# 7688_kernel.net
KiCad netlist of a schematic drawn in Altium Designer
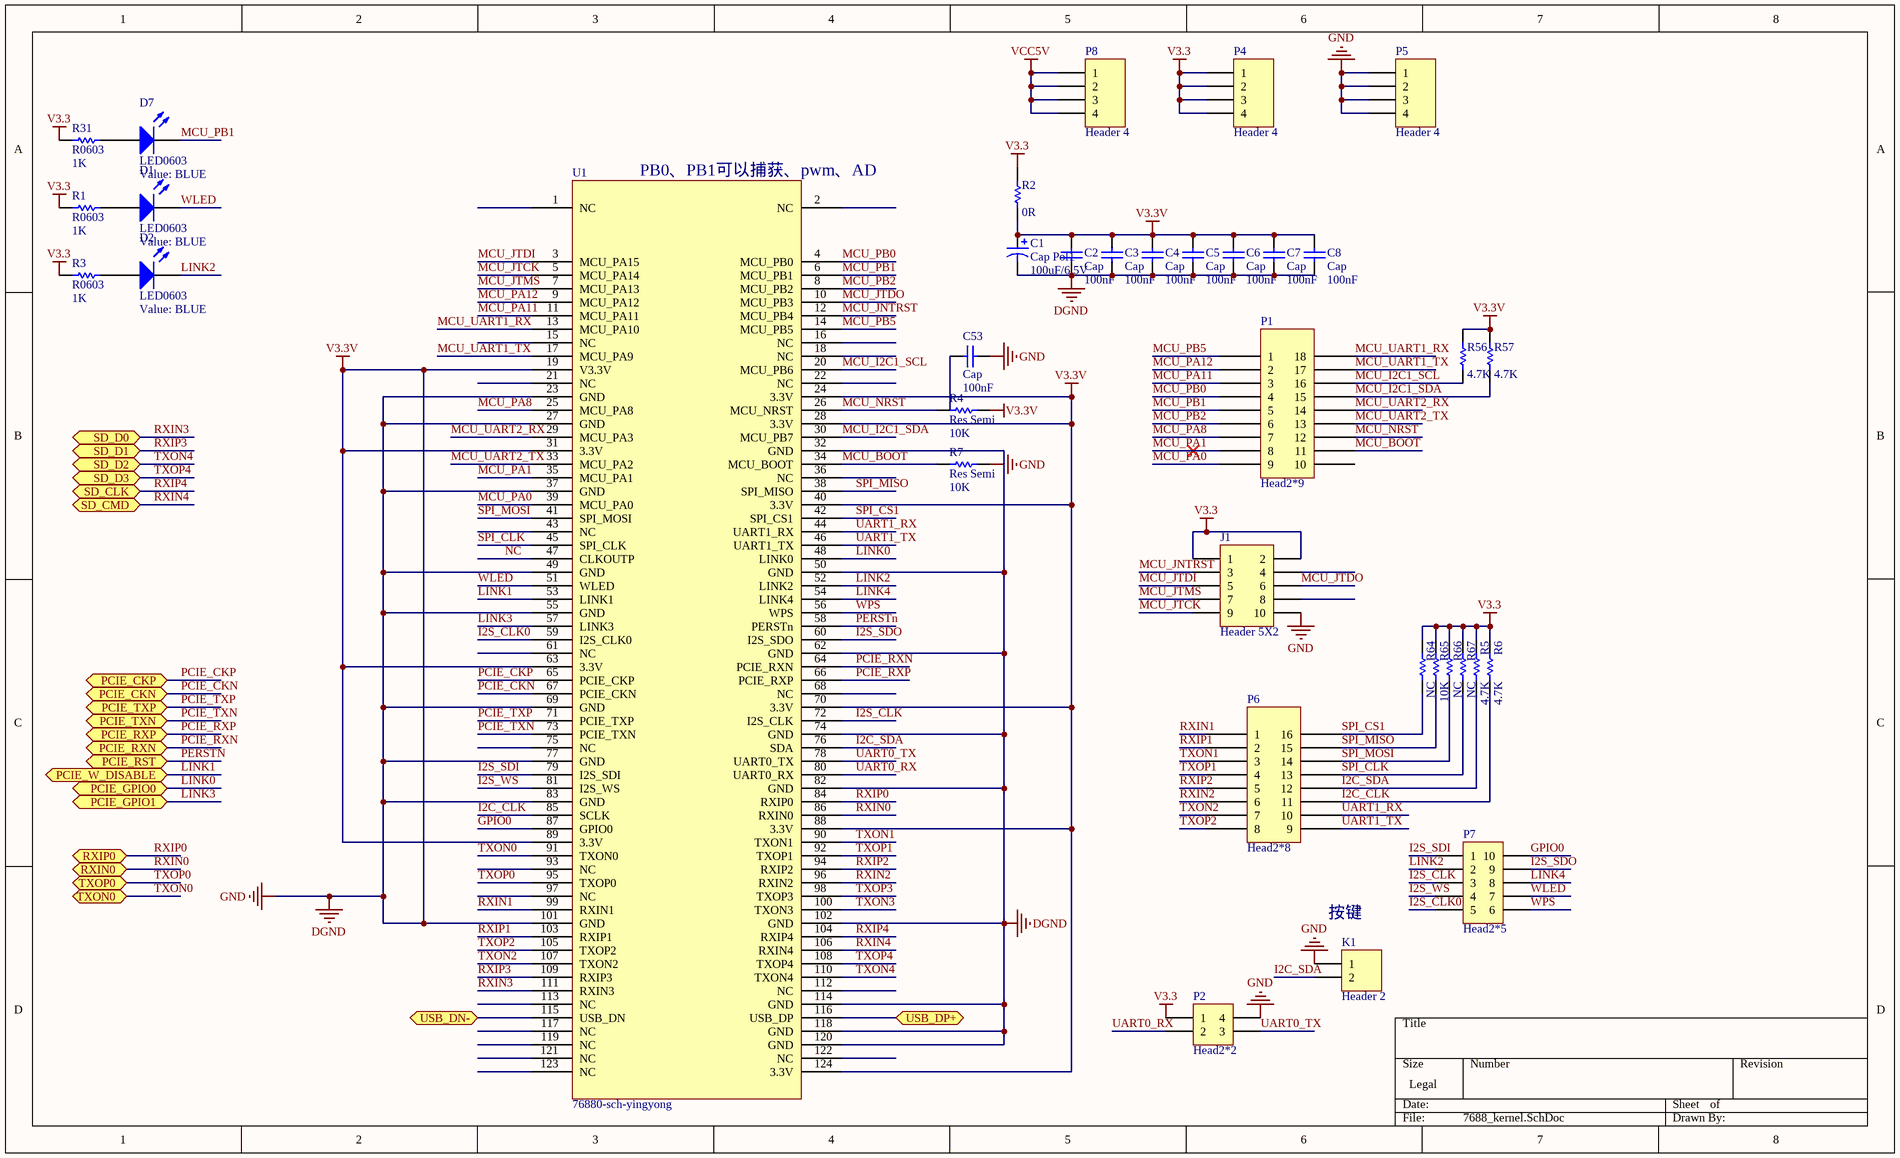
[diagram p0: 7688_kernel.SchDoc]

(export (version "E")
  (design (tool "Eeschema 10.0.6"))
  (components
    (comp (ref "C1")
      (value "Cap Pol1")
      (footprint "C1210-A")
      (description "Polarized Capacitor (Radial)")
      (fields (field (name "ALTIUM_VALUE") "100uF/6.5V") (field (name "PUBLISHER") "Altium Limited"))
      (libsource (lib "Miscellaneous Devices") (part "Cap Pol1"))
    )
    (comp (ref "C2")
      (value "Cap")
      (footprint "R0603N")
      (description "Capacitor")
      (fields (field (name "ALTIUM_VALUE") "100nF") (field (name "PUBLISHER") "Altium Limited"))
      (libsource (lib "Miscellaneous Devices") (part "Cap"))
    )
    (comp (ref "C3")
      (value "Cap")
      (footprint "R0603N")
      (description "Capacitor")
      (fields (field (name "ALTIUM_VALUE") "100nF") (field (name "PUBLISHER") "Altium Limited"))
      (libsource (lib "Miscellaneous Devices") (part "Cap"))
    )
    (comp (ref "C4")
      (value "Cap")
      (footprint "R0603N")
      (description "Capacitor")
      (fields (field (name "ALTIUM_VALUE") "100nF") (field (name "PUBLISHER") "Altium Limited"))
      (libsource (lib "Miscellaneous Devices") (part "Cap"))
    )
    (comp (ref "C5")
      (value "Cap")
      (footprint "R0603N")
      (description "Capacitor")
      (fields (field (name "ALTIUM_VALUE") "100nF") (field (name "PUBLISHER") "Altium Limited"))
      (libsource (lib "Miscellaneous Devices") (part "Cap"))
    )
    (comp (ref "C6")
      (value "Cap")
      (footprint "R0603N")
      (description "Capacitor")
      (fields (field (name "ALTIUM_VALUE") "100nF") (field (name "PUBLISHER") "Altium Limited"))
      (libsource (lib "Miscellaneous Devices") (part "Cap"))
    )
    (comp (ref "C7")
      (value "Cap")
      (footprint "R0603N")
      (description "Capacitor")
      (fields (field (name "ALTIUM_VALUE") "100nF") (field (name "PUBLISHER") "Altium Limited"))
      (libsource (lib "Miscellaneous Devices") (part "Cap"))
    )
    (comp (ref "C8")
      (value "Cap")
      (footprint "R0603N")
      (description "Capacitor")
      (fields (field (name "ALTIUM_VALUE") "100nF") (field (name "PUBLISHER") "Altium Limited"))
      (libsource (lib "Miscellaneous Devices") (part "Cap"))
    )
    (comp (ref "C53")
      (value "Cap")
      (footprint "R0603N")
      (description "Capacitor")
      (fields (field (name "ALTIUM_VALUE") "100nF") (field (name "PUBLISHER") "Altium Limited"))
      (libsource (lib "Miscellaneous Devices") (part "Cap"))
    )
    (comp (ref "D1")
      (value "LED0603")
      (footprint "LED0603")
      (description "LED")
      (fields (field (name "ALTIUM_VALUE") "BLUE"))
      (libsource (lib "schumyhao's_Device") (part "LED"))
    )
    (comp (ref "D2")
      (value "LED0603")
      (footprint "LED0603")
      (description "LED")
      (fields (field (name "ALTIUM_VALUE") "BLUE"))
      (libsource (lib "schumyhao's_Device") (part "LED"))
    )
    (comp (ref "D7")
      (value "LED0603")
      (footprint "LED0603")
      (description "LED")
      (fields (field (name "ALTIUM_VALUE") "BLUE"))
      (libsource (lib "schumyhao's_Device") (part "LED"))
    )
    (comp (ref "J1")
      (value "Header 5X2")
      (footprint "JTAG-10PIN")
      (description "Header, 5-Pin, Dual row")
      (fields (field (name "PUBLISHER") "Altium Limited"))
      (libsource (lib "Miscellaneous Connectors") (part "Header 5X2"))
    )
    (comp (ref "K1")
      (value "Header 2")
      (footprint "3*6key")
      (description "Header, 2-Pin")
      (fields (field (name "PUBLISHER") "Altium Limited"))
      (libsource (lib "Miscellaneous Connectors") (part "Header 2"))
    )
    (comp (ref "P1")
      (value "Head2*9")
      (footprint "Head2*9-tie")
      (libsource (lib "Interface") (part "Head2*9"))
    )
    (comp (ref "P2")
      (value "Head2*2")
      (footprint "Head2*2-tie")
      (libsource (lib "Interface") (part "Head2*2"))
    )
    (comp (ref "P4")
      (value "Header 4")
      (footprint "HDR1X4")
      (description "Header, 4-Pin")
      (fields (field (name "PUBLISHER") "Altium Limited"))
      (libsource (lib "Miscellaneous Connectors") (part "Header 4"))
    )
    (comp (ref "P5")
      (value "Header 4")
      (footprint "HDR1X4")
      (description "Header, 4-Pin")
      (fields (field (name "PUBLISHER") "Altium Limited"))
      (libsource (lib "Miscellaneous Connectors") (part "Header 4"))
    )
    (comp (ref "P6")
      (value "Head2*8")
      (footprint "Head2*8_tie")
      (libsource (lib "Interface") (part "Head2*8"))
    )
    (comp (ref "P7")
      (value "Head2*5")
      (footprint "Head2*5-tie")
      (libsource (lib "Interface") (part "Head2*5"))
    )
    (comp (ref "P8")
      (value "Header 4")
      (footprint "HDR1X4")
      (description "Header, 4-Pin")
      (fields (field (name "PUBLISHER") "Altium Limited"))
      (libsource (lib "Miscellaneous Connectors") (part "Header 4"))
    )
    (comp (ref "R1")
      (value "R0603")
      (footprint "R0603N")
      (description "Semiconductor Resistor")
      (fields (field (name "ALTIUM_VALUE") "1K"))
      (libsource (lib "schumyhao's_Device") (part "Res Semi"))
    )
    (comp (ref "R2")
      (value "0R")
      (footprint "R0805N")
      (description "Semiconductor Resistor")
      (fields (field (name "PUBLISHER") "Altium Limited"))
      (libsource (lib "Miscellaneous Devices") (part "Res Semi"))
    )
    (comp (ref "R3")
      (value "R0603")
      (footprint "R0603N")
      (description "Semiconductor Resistor")
      (fields (field (name "ALTIUM_VALUE") "1K"))
      (libsource (lib "schumyhao's_Device") (part "Res Semi"))
    )
    (comp (ref "R4")
      (value "Res Semi")
      (footprint "R0603N")
      (description "Semiconductor Resistor")
      (fields (field (name "ALTIUM_VALUE") "10K") (field (name "PUBLISHER") "Altium Limited"))
      (libsource (lib "Miscellaneous Devices") (part "Res Semi"))
    )
    (comp (ref "R5")
      (value "4.7K")
      (footprint "R0603N")
      (description "Semiconductor Resistor")
      (fields (field (name "PUBLISHER") "Altium Limited"))
      (libsource (lib "Miscellaneous Devices") (part "Res Semi"))
    )
    (comp (ref "R6")
      (value "4.7K")
      (footprint "R0603N")
      (description "Semiconductor Resistor")
      (fields (field (name "PUBLISHER") "Altium Limited"))
      (libsource (lib "Miscellaneous Devices") (part "Res Semi"))
    )
    (comp (ref "R7")
      (value "Res Semi")
      (footprint "R0603N")
      (description "Semiconductor Resistor")
      (fields (field (name "ALTIUM_VALUE") "10K") (field (name "PUBLISHER") "Altium Limited"))
      (libsource (lib "Miscellaneous Devices") (part "Res Semi"))
    )
    (comp (ref "R31")
      (value "R0603")
      (footprint "R0603N")
      (description "Semiconductor Resistor")
      (fields (field (name "ALTIUM_VALUE") "1K"))
      (libsource (lib "schumyhao's_Device") (part "Res Semi"))
    )
    (comp (ref "R56")
      (value "4.7K")
      (footprint "R0603N")
      (description "Semiconductor Resistor")
      (fields (field (name "PUBLISHER") "Altium Limited"))
      (libsource (lib "Miscellaneous Devices") (part "Res Semi"))
    )
    (comp (ref "R57")
      (value "4.7K")
      (footprint "R0603N")
      (description "Semiconductor Resistor")
      (fields (field (name "PUBLISHER") "Altium Limited"))
      (libsource (lib "Miscellaneous Devices") (part "Res Semi"))
    )
    (comp (ref "R64")
      (value "NC")
      (footprint "R0603N")
      (description "Semiconductor Resistor")
      (fields (field (name "PUBLISHER") "Altium Limited"))
      (libsource (lib "Miscellaneous Devices") (part "Res Semi"))
    )
    (comp (ref "R65")
      (value "10K")
      (footprint "R0603N")
      (description "Semiconductor Resistor")
      (fields (field (name "PUBLISHER") "Altium Limited"))
      (libsource (lib "Miscellaneous Devices") (part "Res Semi"))
    )
    (comp (ref "R66")
      (value "NC")
      (footprint "R0603N")
      (description "Semiconductor Resistor")
      (fields (field (name "PUBLISHER") "Altium Limited"))
      (libsource (lib "Miscellaneous Devices") (part "Res Semi"))
    )
    (comp (ref "R67")
      (value "NC")
      (footprint "R0603N")
      (description "Semiconductor Resistor")
      (libsource (lib "Miscellaneous Devices") (part "Res Semi"))
    )
    (comp (ref "U1")
      (value "76880-sch-yingyong")
      (footprint "MINI-PCI-BZ")
      (libsource (lib "Schlib1") (part "76880-sch-yingyong"))
    )
  )
  (nets
    (net (code "1") (name "/GPIO0") (class "Default")
      (node (ref "P7") (pin "10") (pinfunction "10_10") (pintype "passive"))
      (node (ref "U1") (pin "87") (pinfunction "GPIO0_87") (pintype "passive"))
    )
    (net (code "2") (name "/I2C_CLK") (class "Default")
      (node (ref "P6") (pin "11") (pinfunction "11_11") (pintype "passive"))
      (node (ref "R6") (pin "1") (pinfunction "1_1") (pintype "passive"))
      (node (ref "U1") (pin "85") (pinfunction "SCLK_85") (pintype "passive"))
    )
    (net (code "3") (name "/I2C_SDA") (class "Default")
      (node (ref "K1") (pin "2") (pinfunction "2_2") (pintype "passive"))
      (node (ref "P6") (pin "12") (pinfunction "12_12") (pintype "passive"))
      (node (ref "R5") (pin "1") (pinfunction "1_1") (pintype "passive"))
      (node (ref "U1") (pin "76") (pinfunction "SDA_76") (pintype "passive"))
    )
    (net (code "4") (name "/I2S_CLK") (class "Default")
      (node (ref "P7") (pin "3") (pinfunction "3_3") (pintype "passive"))
      (node (ref "U1") (pin "72") (pinfunction "I2S_CLK_72") (pintype "passive"))
    )
    (net (code "5") (name "/I2S_CLK0") (class "Default")
      (node (ref "P7") (pin "5") (pinfunction "5_5") (pintype "passive"))
      (node (ref "U1") (pin "59") (pinfunction "I2S_CLK0_59") (pintype "passive"))
    )
    (net (code "6") (name "/I2S_SDI") (class "Default")
      (node (ref "P7") (pin "1") (pinfunction "1_1") (pintype "passive"))
      (node (ref "U1") (pin "79") (pinfunction "I2S_SDI_79") (pintype "passive"))
    )
    (net (code "7") (name "/I2S_SDO") (class "Default")
      (node (ref "P7") (pin "9") (pinfunction "9_9") (pintype "passive"))
      (node (ref "U1") (pin "60") (pinfunction "I2S_SDO_60") (pintype "passive"))
    )
    (net (code "8") (name "/I2S_WS") (class "Default")
      (node (ref "P7") (pin "4") (pinfunction "4_4") (pintype "passive"))
      (node (ref "U1") (pin "81") (pinfunction "I2S_WS_81") (pintype "passive"))
    )
    (net (code "9") (name "/LINK0") (class "Default")
      (node (ref "U1") (pin "48") (pinfunction "LINK0_48") (pintype "passive"))
    )
    (net (code "10") (name "/LINK1") (class "Default")
      (node (ref "U1") (pin "53") (pinfunction "LINK1_53") (pintype "passive"))
    )
    (net (code "11") (name "/LINK2") (class "Default")
      (node (ref "D2") (pin "2") (pinfunction "2_2") (pintype "passive"))
      (node (ref "P7") (pin "2") (pinfunction "2_2") (pintype "passive"))
      (node (ref "U1") (pin "52") (pinfunction "LINK2_52") (pintype "passive"))
    )
    (net (code "12") (name "/LINK3") (class "Default")
      (node (ref "U1") (pin "57") (pinfunction "LINK3_57") (pintype "passive"))
    )
    (net (code "13") (name "/LINK4") (class "Default")
      (node (ref "P7") (pin "8") (pinfunction "8_8") (pintype "passive"))
      (node (ref "U1") (pin "54") (pinfunction "LINK4_54") (pintype "passive"))
    )
    (net (code "14") (name "/MCU_BOOT") (class "Default")
      (node (ref "P1") (pin "11") (pinfunction "11_11") (pintype "passive"))
      (node (ref "R7") (pin "1") (pinfunction "1_1") (pintype "passive"))
      (node (ref "U1") (pin "34") (pinfunction "MCU_BOOT_34") (pintype "passive"))
    )
    (net (code "15") (name "/MCU_I2C1_SCL") (class "Default")
      (node (ref "P1") (pin "16") (pinfunction "16_16") (pintype "passive"))
      (node (ref "R56") (pin "1") (pinfunction "1_1") (pintype "passive"))
      (node (ref "U1") (pin "20") (pinfunction "MCU_PB6_20") (pintype "passive"))
    )
    (net (code "16") (name "/MCU_I2C1_SDA") (class "Default")
      (node (ref "P1") (pin "15") (pinfunction "15_15") (pintype "passive"))
      (node (ref "R57") (pin "1") (pinfunction "1_1") (pintype "passive"))
      (node (ref "U1") (pin "30") (pinfunction "MCU_PB7_30") (pintype "passive"))
    )
    (net (code "17") (name "/MCU_JNTRST") (class "Default")
      (node (ref "J1") (pin "3") (pinfunction "3_3") (pintype "passive"))
      (node (ref "U1") (pin "12") (pinfunction "MCU_PB4_12") (pintype "passive"))
    )
    (net (code "18") (name "/MCU_JTCK") (class "Default")
      (node (ref "J1") (pin "9") (pinfunction "9_9") (pintype "passive"))
      (node (ref "U1") (pin "5") (pinfunction "MCU_PA14_5") (pintype "passive"))
    )
    (net (code "19") (name "/MCU_JTDI") (class "Default")
      (node (ref "J1") (pin "5") (pinfunction "5_5") (pintype "passive"))
      (node (ref "U1") (pin "3") (pinfunction "MCU_PA15_3") (pintype "passive"))
    )
    (net (code "20") (name "/MCU_JTDO") (class "Default")
      (node (ref "J1") (pin "6") (pinfunction "6_6") (pintype "passive"))
      (node (ref "U1") (pin "10") (pinfunction "MCU_PB3_10") (pintype "passive"))
    )
    (net (code "21") (name "/MCU_JTMS") (class "Default")
      (node (ref "J1") (pin "7") (pinfunction "7_7") (pintype "passive"))
      (node (ref "U1") (pin "7") (pinfunction "MCU_PA13_7") (pintype "passive"))
    )
    (net (code "22") (name "/MCU_NRST") (class "Default")
      (node (ref "P1") (pin "12") (pinfunction "12_12") (pintype "passive"))
      (node (ref "R4") (pin "1") (pinfunction "1_1") (pintype "passive"))
      (node (ref "U1") (pin "26") (pinfunction "MCU_NRST_26") (pintype "passive"))
    )
    (net (code "23") (name "/MCU_PA0") (class "Default")
      (node (ref "P1") (pin "9") (pinfunction "9_9") (pintype "passive"))
      (node (ref "U1") (pin "39") (pinfunction "MCU_PA0_39") (pintype "passive"))
    )
    (net (code "24") (name "/MCU_PA1") (class "Default")
      (node (ref "P1") (pin "8") (pinfunction "8_8") (pintype "passive"))
      (node (ref "U1") (pin "35") (pinfunction "MCU_PA1_35") (pintype "passive"))
    )
    (net (code "25") (name "/MCU_PA8") (class "Default")
      (node (ref "P1") (pin "7") (pinfunction "7_7") (pintype "passive"))
      (node (ref "U1") (pin "25") (pinfunction "MCU_PA8_25") (pintype "passive"))
    )
    (net (code "26") (name "/MCU_PA11") (class "Default")
      (node (ref "P1") (pin "3") (pinfunction "3_3") (pintype "passive"))
      (node (ref "U1") (pin "11") (pinfunction "MCU_PA11_11") (pintype "passive"))
    )
    (net (code "27") (name "/MCU_PA12") (class "Default")
      (node (ref "P1") (pin "2") (pinfunction "2_2") (pintype "passive"))
      (node (ref "U1") (pin "9") (pinfunction "MCU_PA12_9") (pintype "passive"))
    )
    (net (code "28") (name "/MCU_PB0") (class "Default")
      (node (ref "P1") (pin "4") (pinfunction "4_4") (pintype "passive"))
      (node (ref "U1") (pin "4") (pinfunction "MCU_PB0_4") (pintype "passive"))
    )
    (net (code "29") (name "/MCU_PB1") (class "Default")
      (node (ref "D7") (pin "2") (pinfunction "2_2") (pintype "passive"))
      (node (ref "P1") (pin "5") (pinfunction "5_5") (pintype "passive"))
      (node (ref "U1") (pin "6") (pinfunction "MCU_PB1_6") (pintype "passive"))
    )
    (net (code "30") (name "/MCU_PB2") (class "Default")
      (node (ref "P1") (pin "6") (pinfunction "6_6") (pintype "passive"))
      (node (ref "U1") (pin "8") (pinfunction "MCU_PB2_8") (pintype "passive"))
    )
    (net (code "31") (name "/MCU_PB5") (class "Default")
      (node (ref "P1") (pin "1") (pinfunction "1_1") (pintype "passive"))
      (node (ref "U1") (pin "14") (pinfunction "MCU_PB5_14") (pintype "passive"))
    )
    (net (code "32") (name "/MCU_UART1_RX") (class "Default")
      (node (ref "P1") (pin "18") (pinfunction "18_18") (pintype "passive"))
      (node (ref "U1") (pin "13") (pinfunction "MCU_PA10_13") (pintype "passive"))
    )
    (net (code "33") (name "/MCU_UART1_TX") (class "Default")
      (node (ref "P1") (pin "17") (pinfunction "17_17") (pintype "passive"))
      (node (ref "U1") (pin "17") (pinfunction "MCU_PA9_17") (pintype "passive"))
    )
    (net (code "34") (name "/MCU_UART2_RX") (class "Default")
      (node (ref "P1") (pin "14") (pinfunction "14_14") (pintype "passive"))
      (node (ref "U1") (pin "29") (pinfunction "MCU_PA3_29") (pintype "passive"))
    )
    (net (code "35") (name "/MCU_UART2_TX") (class "Default")
      (node (ref "P1") (pin "13") (pinfunction "13_13") (pintype "passive"))
      (node (ref "U1") (pin "33") (pinfunction "MCU_PA2_33") (pintype "passive"))
    )
    (net (code "36") (name "/NC") (class "Default")
      (node (ref "U1") (pin "47") (pinfunction "CLKOUTP_47") (pintype "passive"))
    )
    (net (code "37") (name "/PCIE_CKN") (class "Default")
      (node (ref "U1") (pin "67") (pinfunction "PCIE_CKN_67") (pintype "passive"))
    )
    (net (code "38") (name "/PCIE_CKP") (class "Default")
      (node (ref "U1") (pin "65") (pinfunction "PCIE_CKP_65") (pintype "passive"))
    )
    (net (code "39") (name "/PCIE_RXN") (class "Default")
      (node (ref "U1") (pin "64") (pinfunction "PCIE_RXN_64") (pintype "passive"))
    )
    (net (code "40") (name "/PCIE_RXP") (class "Default")
      (node (ref "U1") (pin "66") (pinfunction "PCIE_RXP_66") (pintype "passive"))
    )
    (net (code "41") (name "/PCIE_TXN") (class "Default")
      (node (ref "U1") (pin "73") (pinfunction "PCIE_TXN_73") (pintype "passive"))
    )
    (net (code "42") (name "/PCIE_TXP") (class "Default")
      (node (ref "U1") (pin "71") (pinfunction "PCIE_TXP_71") (pintype "passive"))
    )
    (net (code "44") (name "/PERSTn") (class "Default")
      (node (ref "U1") (pin "58") (pinfunction "PERSTn_58") (pintype "passive"))
    )
    (net (code "45") (name "/RXIN0") (class "Default")
      (node (ref "U1") (pin "86") (pinfunction "RXIN0_86") (pintype "passive"))
    )
    (net (code "46") (name "/RXIN1") (class "Default")
      (node (ref "P6") (pin "1") (pinfunction "1_1") (pintype "passive"))
      (node (ref "U1") (pin "99") (pinfunction "RXIN1_99") (pintype "passive"))
    )
    (net (code "47") (name "/RXIN2") (class "Default")
      (node (ref "P6") (pin "6") (pinfunction "6_6") (pintype "passive"))
      (node (ref "U1") (pin "96") (pinfunction "RXIN2_96") (pintype "passive"))
    )
    (net (code "48") (name "/RXIN3") (class "Default")
      (node (ref "U1") (pin "111") (pinfunction "RXIN3_111") (pintype "passive"))
    )
    (net (code "49") (name "/RXIN4") (class "Default")
      (node (ref "U1") (pin "106") (pinfunction "RXIN4_106") (pintype "passive"))
    )
    (net (code "50") (name "/RXIP0") (class "Default")
      (node (ref "U1") (pin "84") (pinfunction "RXIP0_84") (pintype "passive"))
    )
    (net (code "51") (name "/RXIP1") (class "Default")
      (node (ref "P6") (pin "2") (pinfunction "2_2") (pintype "passive"))
      (node (ref "U1") (pin "103") (pinfunction "RXIP1_103") (pintype "passive"))
    )
    (net (code "52") (name "/RXIP2") (class "Default")
      (node (ref "P6") (pin "5") (pinfunction "5_5") (pintype "passive"))
      (node (ref "U1") (pin "94") (pinfunction "RXIP2_94") (pintype "passive"))
    )
    (net (code "53") (name "/RXIP3") (class "Default")
      (node (ref "U1") (pin "109") (pinfunction "RXIP3_109") (pintype "passive"))
    )
    (net (code "54") (name "/RXIP4") (class "Default")
      (node (ref "U1") (pin "104") (pinfunction "RXIP4_104") (pintype "passive"))
    )
    (net (code "55") (name "/SPI_CLK") (class "Default")
      (node (ref "P6") (pin "13") (pinfunction "13_13") (pintype "passive"))
      (node (ref "R67") (pin "1") (pinfunction "1_1") (pintype "passive"))
      (node (ref "U1") (pin "45") (pinfunction "SPI_CLK_45") (pintype "passive"))
    )
    (net (code "56") (name "/SPI_CS1") (class "Default")
      (node (ref "P6") (pin "16") (pinfunction "16_16") (pintype "passive"))
      (node (ref "R64") (pin "1") (pinfunction "1_1") (pintype "passive"))
      (node (ref "U1") (pin "42") (pinfunction "SPI_CS1_42") (pintype "passive"))
    )
    (net (code "57") (name "/SPI_MISO") (class "Default")
      (node (ref "P6") (pin "15") (pinfunction "15_15") (pintype "passive"))
      (node (ref "R65") (pin "1") (pinfunction "1_1") (pintype "passive"))
      (node (ref "U1") (pin "38") (pinfunction "SPI_MISO_38") (pintype "passive"))
    )
    (net (code "58") (name "/SPI_MOSI") (class "Default")
      (node (ref "P6") (pin "14") (pinfunction "14_14") (pintype "passive"))
      (node (ref "R66") (pin "1") (pinfunction "1_1") (pintype "passive"))
      (node (ref "U1") (pin "41") (pinfunction "SPI_MOSI_41") (pintype "passive"))
    )
    (net (code "59") (name "/TXON0") (class "Default")
      (node (ref "U1") (pin "91") (pinfunction "TXON0_91") (pintype "passive"))
    )
    (net (code "60") (name "/TXON1") (class "Default")
      (node (ref "P6") (pin "3") (pinfunction "3_3") (pintype "passive"))
      (node (ref "U1") (pin "90") (pinfunction "TXON1_90") (pintype "passive"))
    )
    (net (code "61") (name "/TXON2") (class "Default")
      (node (ref "P6") (pin "7") (pinfunction "7_7") (pintype "passive"))
      (node (ref "U1") (pin "107") (pinfunction "TXON2_107") (pintype "passive"))
    )
    (net (code "62") (name "/TXON3") (class "Default")
      (node (ref "U1") (pin "100") (pinfunction "TXON3_100") (pintype "passive"))
    )
    (net (code "63") (name "/TXON4") (class "Default")
      (node (ref "U1") (pin "110") (pinfunction "TXON4_110") (pintype "passive"))
    )
    (net (code "64") (name "/TXOP0") (class "Default")
      (node (ref "U1") (pin "95") (pinfunction "TXOP0_95") (pintype "passive"))
    )
    (net (code "65") (name "/TXOP1") (class "Default")
      (node (ref "P6") (pin "4") (pinfunction "4_4") (pintype "passive"))
      (node (ref "U1") (pin "92") (pinfunction "TXOP1_92") (pintype "passive"))
    )
    (net (code "66") (name "/TXOP2") (class "Default")
      (node (ref "P6") (pin "8") (pinfunction "8_8") (pintype "passive"))
      (node (ref "U1") (pin "105") (pinfunction "TXOP2_105") (pintype "passive"))
    )
    (net (code "67") (name "/TXOP3") (class "Default")
      (node (ref "U1") (pin "98") (pinfunction "TXOP3_98") (pintype "passive"))
    )
    (net (code "68") (name "/TXOP4") (class "Default")
      (node (ref "U1") (pin "108") (pinfunction "TXOP4_108") (pintype "passive"))
    )
    (net (code "69") (name "/UART0_RX") (class "Default")
      (node (ref "P2") (pin "2") (pinfunction "2_2") (pintype "passive"))
      (node (ref "U1") (pin "80") (pinfunction "UART0_RX_80") (pintype "passive"))
    )
    (net (code "70") (name "/UART0_TX") (class "Default")
      (node (ref "P2") (pin "3") (pinfunction "3_3") (pintype "passive"))
      (node (ref "U1") (pin "78") (pinfunction "UART0_TX_78") (pintype "passive"))
    )
    (net (code "71") (name "/UART1_RX") (class "Default")
      (node (ref "P6") (pin "10") (pinfunction "10_10") (pintype "passive"))
      (node (ref "U1") (pin "44") (pinfunction "UART1_RX_44") (pintype "passive"))
    )
    (net (code "72") (name "/UART1_TX") (class "Default")
      (node (ref "P6") (pin "9") (pinfunction "9_9") (pintype "passive"))
      (node (ref "U1") (pin "46") (pinfunction "UART1_TX_46") (pintype "passive"))
    )
    (net (code "73") (name "/USB_DN-") (class "Default")
      (node (ref "U1") (pin "115") (pinfunction "USB_DN_115") (pintype "passive"))
    )
    (net (code "74") (name "/USB_DP+") (class "Default")
      (node (ref "U1") (pin "116") (pinfunction "USB_DP_116") (pintype "passive"))
    )
    (net (code "75") (name "/WLED") (class "Default")
      (node (ref "D1") (pin "2") (pinfunction "2_2") (pintype "passive"))
      (node (ref "P7") (pin "7") (pinfunction "7_7") (pintype "passive"))
      (node (ref "U1") (pin "51") (pinfunction "WLED_51") (pintype "passive"))
    )
    (net (code "76") (name "/WPS") (class "Default")
      (node (ref "P7") (pin "6") (pinfunction "6_6") (pintype "passive"))
      (node (ref "U1") (pin "56") (pinfunction "WPS_56") (pintype "passive"))
    )
    (net (code "77") (name "DGND") (class "Default")
      (node (ref "C1") (pin "1") (pinfunction "1_1") (pintype "passive"))
      (node (ref "C1") (pin "2") (pinfunction "2_2") (pintype "passive"))
      (node (ref "C2") (pin "1") (pinfunction "1_1") (pintype "passive"))
      (node (ref "C2") (pin "2") (pinfunction "2_2") (pintype "passive"))
      (node (ref "C3") (pin "1") (pinfunction "1_1") (pintype "passive"))
      (node (ref "C3") (pin "2") (pinfunction "2_2") (pintype "passive"))
      (node (ref "C4") (pin "1") (pinfunction "1_1") (pintype "passive"))
      (node (ref "C4") (pin "2") (pinfunction "2_2") (pintype "passive"))
      (node (ref "C5") (pin "1") (pinfunction "1_1") (pintype "passive"))
      (node (ref "C5") (pin "2") (pinfunction "2_2") (pintype "passive"))
      (node (ref "C53") (pin "2") (pinfunction "2_2") (pintype "passive"))
      (node (ref "C6") (pin "1") (pinfunction "1_1") (pintype "passive"))
      (node (ref "C6") (pin "2") (pinfunction "2_2") (pintype "passive"))
      (node (ref "C7") (pin "1") (pinfunction "1_1") (pintype "passive"))
      (node (ref "C7") (pin "2") (pinfunction "2_2") (pintype "passive"))
      (node (ref "C8") (pin "1") (pinfunction "1_1") (pintype "passive"))
      (node (ref "C8") (pin "2") (pinfunction "2_2") (pintype "passive"))
      (node (ref "J1") (pin "10") (pinfunction "10_10") (pintype "passive"))
      (node (ref "K1") (pin "1") (pinfunction "1_1") (pintype "passive"))
      (node (ref "P2") (pin "4") (pinfunction "4_4") (pintype "passive"))
      (node (ref "P5") (pin "1") (pinfunction "1_1") (pintype "passive"))
      (node (ref "P5") (pin "2") (pinfunction "2_2") (pintype "passive"))
      (node (ref "P5") (pin "3") (pinfunction "3_3") (pintype "passive"))
      (node (ref "P5") (pin "4") (pinfunction "4_4") (pintype "passive"))
      (node (ref "R2") (pin "1") (pinfunction "1_1") (pintype "passive"))
      (node (ref "R4") (pin "2") (pinfunction "2_2") (pintype "passive"))
      (node (ref "R56") (pin "2") (pinfunction "2_2") (pintype "passive"))
      (node (ref "R57") (pin "2") (pinfunction "2_2") (pintype "passive"))
      (node (ref "R7") (pin "2") (pinfunction "2_2") (pintype "passive"))
      (node (ref "U1") (pin "101") (pinfunction "GND_101") (pintype "passive"))
      (node (ref "U1") (pin "102") (pinfunction "GND_102") (pintype "passive"))
      (node (ref "U1") (pin "114") (pinfunction "GND_114") (pintype "passive"))
      (node (ref "U1") (pin "118") (pinfunction "GND_118") (pintype "passive"))
      (node (ref "U1") (pin "120") (pinfunction "GND_120") (pintype "passive"))
      (node (ref "U1") (pin "124") (pinfunction "3.3V_124") (pintype "passive"))
      (node (ref "U1") (pin "19") (pinfunction "V3.3V_19") (pintype "passive"))
      (node (ref "U1") (pin "23") (pinfunction "GND_23") (pintype "passive"))
      (node (ref "U1") (pin "24") (pinfunction "3.3V_24") (pintype "passive"))
      (node (ref "U1") (pin "27") (pinfunction "GND_27") (pintype "passive"))
      (node (ref "U1") (pin "28") (pinfunction "3.3V_28") (pintype "passive"))
      (node (ref "U1") (pin "31") (pinfunction "3.3V_31") (pintype "passive"))
      (node (ref "U1") (pin "32") (pinfunction "GND_32") (pintype "passive"))
      (node (ref "U1") (pin "37") (pinfunction "GND_37") (pintype "passive"))
      (node (ref "U1") (pin "40") (pinfunction "3.3V_40") (pintype "passive"))
      (node (ref "U1") (pin "49") (pinfunction "GND_49") (pintype "passive"))
      (node (ref "U1") (pin "50") (pinfunction "GND_50") (pintype "passive"))
      (node (ref "U1") (pin "55") (pinfunction "GND_55") (pintype "passive"))
      (node (ref "U1") (pin "62") (pinfunction "GND_62") (pintype "passive"))
      (node (ref "U1") (pin "63") (pinfunction "3.3V_63") (pintype "passive"))
      (node (ref "U1") (pin "69") (pinfunction "GND_69") (pintype "passive"))
      (node (ref "U1") (pin "70") (pinfunction "3.3V_70") (pintype "passive"))
      (node (ref "U1") (pin "74") (pinfunction "GND_74") (pintype "passive"))
      (node (ref "U1") (pin "77") (pinfunction "GND_77") (pintype "passive"))
      (node (ref "U1") (pin "82") (pinfunction "GND_82") (pintype "passive"))
      (node (ref "U1") (pin "83") (pinfunction "GND_83") (pintype "passive"))
      (node (ref "U1") (pin "88") (pinfunction "3.3V_88") (pintype "passive"))
      (node (ref "U1") (pin "89") (pinfunction "3.3V_89") (pintype "passive"))
    )
    (net (code "78") (name "Net-(D1-Pad1)") (class "Default")
      (node (ref "D1") (pin "1") (pinfunction "1_1") (pintype "passive"))
      (node (ref "R1") (pin "2") (pinfunction "2_2") (pintype "passive"))
    )
    (net (code "79") (name "Net-(D2-Pad1)") (class "Default")
      (node (ref "D2") (pin "1") (pinfunction "1_1") (pintype "passive"))
      (node (ref "R3") (pin "2") (pinfunction "2_2") (pintype "passive"))
    )
    (net (code "80") (name "Net-(D7-Pad1)") (class "Default")
      (node (ref "D7") (pin "1") (pinfunction "1_1") (pintype "passive"))
      (node (ref "R31") (pin "2") (pinfunction "2_2") (pintype "passive"))
    )
    (net (code "81") (name "V3.3") (class "Default")
      (node (ref "J1") (pin "1") (pinfunction "1_1") (pintype "passive"))
      (node (ref "J1") (pin "2") (pinfunction "2_2") (pintype "passive"))
      (node (ref "P2") (pin "1") (pinfunction "1_1") (pintype "passive"))
      (node (ref "P4") (pin "1") (pinfunction "1_1") (pintype "passive"))
      (node (ref "P4") (pin "2") (pinfunction "2_2") (pintype "passive"))
      (node (ref "P4") (pin "3") (pinfunction "3_3") (pintype "passive"))
      (node (ref "P4") (pin "4") (pinfunction "4_4") (pintype "passive"))
      (node (ref "R1") (pin "1") (pinfunction "1_1") (pintype "passive"))
      (node (ref "R2") (pin "2") (pinfunction "2_2") (pintype "passive"))
      (node (ref "R3") (pin "1") (pinfunction "1_1") (pintype "passive"))
      (node (ref "R31") (pin "1") (pinfunction "1_1") (pintype "passive"))
      (node (ref "R5") (pin "2") (pinfunction "2_2") (pintype "passive"))
      (node (ref "R6") (pin "2") (pinfunction "2_2") (pintype "passive"))
      (node (ref "R64") (pin "2") (pinfunction "2_2") (pintype "passive"))
      (node (ref "R65") (pin "2") (pinfunction "2_2") (pintype "passive"))
      (node (ref "R66") (pin "2") (pinfunction "2_2") (pintype "passive"))
      (node (ref "R67") (pin "2") (pinfunction "2_2") (pintype "passive"))
    )
    (net (code "82") (name "VCC5V") (class "Default")
      (node (ref "P8") (pin "1") (pinfunction "1_1") (pintype "passive"))
      (node (ref "P8") (pin "2") (pinfunction "2_2") (pintype "passive"))
      (node (ref "P8") (pin "3") (pinfunction "3_3") (pintype "passive"))
      (node (ref "P8") (pin "4") (pinfunction "4_4") (pintype "passive"))
    )
    (net (code "83") (name "unconnected-(C53-Pad1)") (class "Default")
      (node (ref "C53") (pin "1") (pinfunction "1_1") (pintype "passive"))
    )
    (net (code "84") (name "unconnected-(J1-Pad4)") (class "Default")
      (node (ref "J1") (pin "4") (pinfunction "4_4") (pintype "passive"))
    )
    (net (code "85") (name "unconnected-(J1-Pad8)") (class "Default")
      (node (ref "J1") (pin "8") (pinfunction "8_8") (pintype "passive"))
    )
    (net (code "86") (name "unconnected-(P1-Pad10)") (class "Default")
      (node (ref "P1") (pin "10") (pinfunction "10_10") (pintype "passive"))
    )
    (net (code "87") (name "unconnected-(U1-NC-Pad1)") (class "Default")
      (node (ref "U1") (pin "1") (pinfunction "NC_1") (pintype "passive"))
    )
    (net (code "88") (name "unconnected-(U1-NC-Pad2)") (class "Default")
      (node (ref "U1") (pin "2") (pinfunction "NC_2") (pintype "passive"))
    )
    (net (code "89") (name "unconnected-(U1-NC-Pad15)") (class "Default")
      (node (ref "U1") (pin "15") (pinfunction "NC_15") (pintype "passive"))
    )
    (net (code "90") (name "unconnected-(U1-NC-Pad16)") (class "Default")
      (node (ref "U1") (pin "16") (pinfunction "NC_16") (pintype "passive"))
    )
    (net (code "91") (name "unconnected-(U1-NC-Pad18)") (class "Default")
      (node (ref "U1") (pin "18") (pinfunction "NC_18") (pintype "passive"))
    )
    (net (code "92") (name "unconnected-(U1-NC-Pad21)") (class "Default")
      (node (ref "U1") (pin "21") (pinfunction "NC_21") (pintype "passive"))
    )
    (net (code "93") (name "unconnected-(U1-NC-Pad22)") (class "Default")
      (node (ref "U1") (pin "22") (pinfunction "NC_22") (pintype "passive"))
    )
    (net (code "94") (name "unconnected-(U1-NC-Pad36)") (class "Default")
      (node (ref "U1") (pin "36") (pinfunction "NC_36") (pintype "passive"))
    )
    (net (code "95") (name "unconnected-(U1-NC-Pad43)") (class "Default")
      (node (ref "U1") (pin "43") (pinfunction "NC_43") (pintype "passive"))
    )
    (net (code "96") (name "unconnected-(U1-NC-Pad61)") (class "Default")
      (node (ref "U1") (pin "61") (pinfunction "NC_61") (pintype "passive"))
    )
    (net (code "97") (name "unconnected-(U1-NC-Pad68)") (class "Default")
      (node (ref "U1") (pin "68") (pinfunction "NC_68") (pintype "passive"))
    )
    (net (code "98") (name "unconnected-(U1-NC-Pad75)") (class "Default")
      (node (ref "U1") (pin "75") (pinfunction "NC_75") (pintype "passive"))
    )
    (net (code "99") (name "unconnected-(U1-NC-Pad93)") (class "Default")
      (node (ref "U1") (pin "93") (pinfunction "NC_93") (pintype "passive"))
    )
    (net (code "100") (name "unconnected-(U1-NC-Pad97)") (class "Default")
      (node (ref "U1") (pin "97") (pinfunction "NC_97") (pintype "passive"))
    )
    (net (code "101") (name "unconnected-(U1-NC-Pad112)") (class "Default")
      (node (ref "U1") (pin "112") (pinfunction "NC_112") (pintype "passive"))
    )
    (net (code "102") (name "unconnected-(U1-NC-Pad113)") (class "Default")
      (node (ref "U1") (pin "113") (pinfunction "NC_113") (pintype "passive"))
    )
    (net (code "103") (name "unconnected-(U1-NC-Pad117)") (class "Default")
      (node (ref "U1") (pin "117") (pinfunction "NC_117") (pintype "passive"))
    )
    (net (code "104") (name "unconnected-(U1-NC-Pad119)") (class "Default")
      (node (ref "U1") (pin "119") (pinfunction "NC_119") (pintype "passive"))
    )
    (net (code "105") (name "unconnected-(U1-NC-Pad121)") (class "Default")
      (node (ref "U1") (pin "121") (pinfunction "NC_121") (pintype "passive"))
    )
    (net (code "106") (name "unconnected-(U1-NC-Pad122)") (class "Default")
      (node (ref "U1") (pin "122") (pinfunction "NC_122") (pintype "passive"))
    )
    (net (code "107") (name "unconnected-(U1-NC-Pad123)") (class "Default")
      (node (ref "U1") (pin "123") (pinfunction "NC_123") (pintype "passive"))
    )
  )
)
